# 30A.net
KiCad netlist of a schematic drawn in Altium Designer
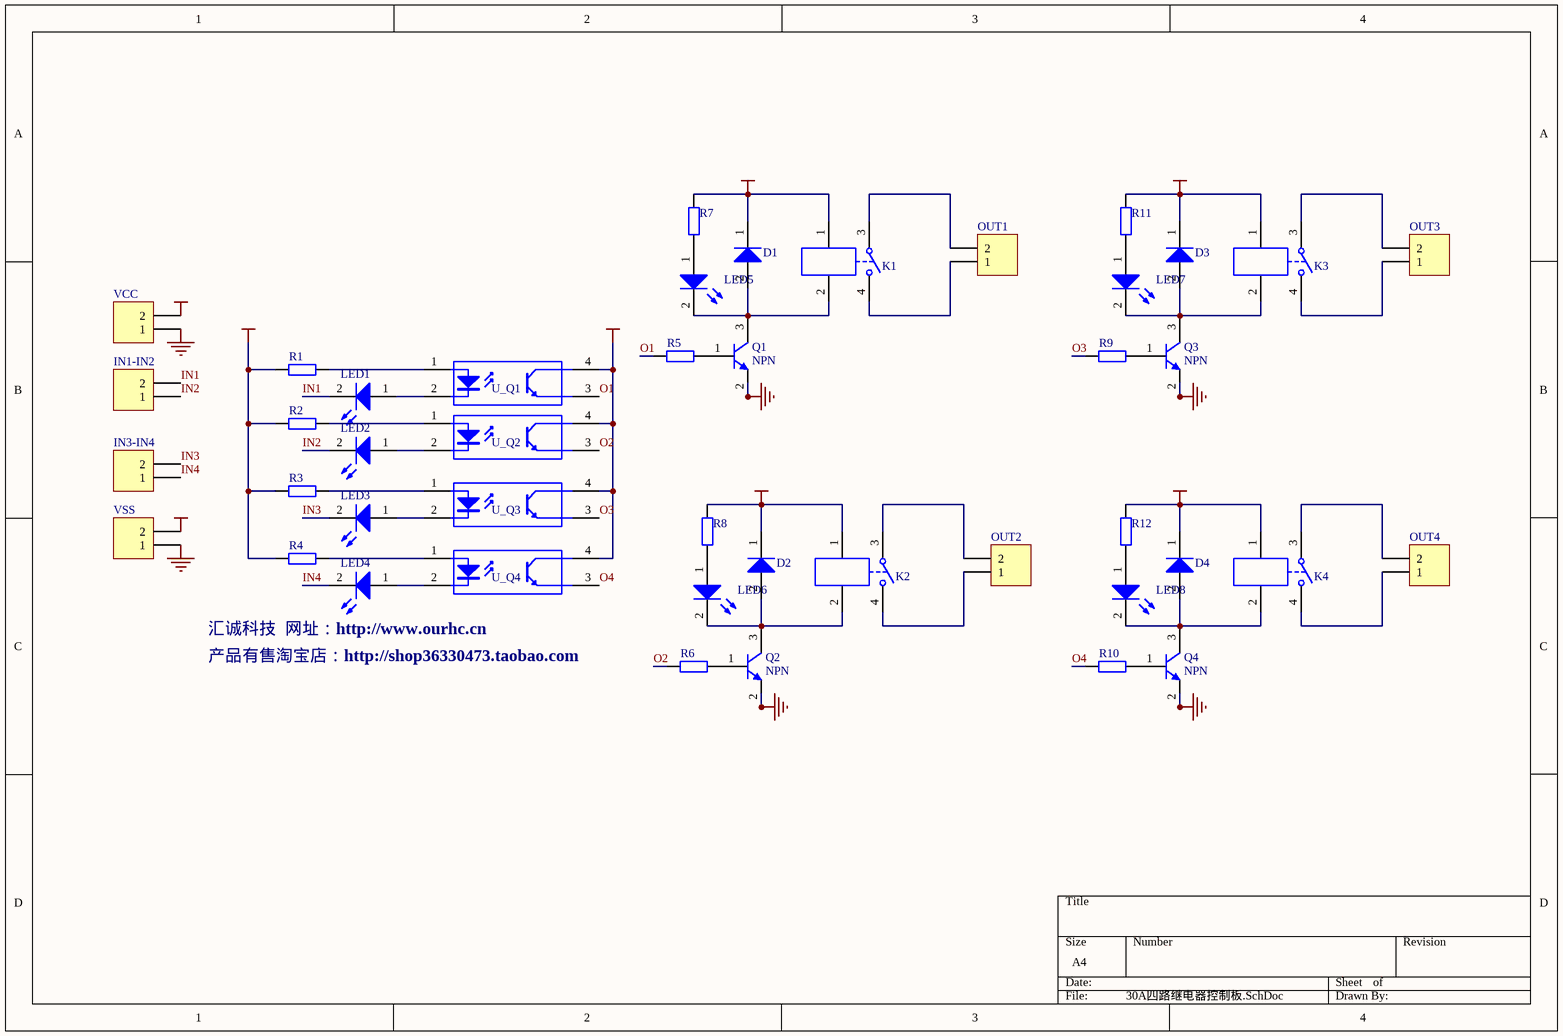
[diagram p0: 30A四路继电器控制板.SchDoc]

(export (version "E")
  (design (tool "Eeschema 10.0.6"))
  (components
    (comp (ref "D1")
      (value "ZL2JG")
      (footprint "7227")
      (description "整流二极管")
      (fields (field (name "PUBLISHER") "Altium Limited"))
      (libsource (lib "zxcourhc") (part "ZL2JG"))
    )
    (comp (ref "D2")
      (value "ZL2JG")
      (footprint "7227")
      (description "整流二极管")
      (fields (field (name "PUBLISHER") "Altium Limited"))
      (libsource (lib "zxcourhc") (part "ZL2JG"))
    )
    (comp (ref "D3")
      (value "ZL2JG")
      (footprint "7227")
      (description "整流二极管")
      (fields (field (name "PUBLISHER") "Altium Limited"))
      (libsource (lib "zxcourhc") (part "ZL2JG"))
    )
    (comp (ref "D4")
      (value "ZL2JG")
      (footprint "7227")
      (description "整流二极管")
      (fields (field (name "PUBLISHER") "Altium Limited"))
      (libsource (lib "zxcourhc") (part "ZL2JG"))
    )
    (comp (ref "IN1-IN2")
      (value "PZ_2")
      (footprint "KF8500-2")
      (description "排针——2")
      (fields (field (name "PUBLISHER") "Altium Limited"))
      (libsource (lib "zxcourhc") (part "PZ_2"))
    )
    (comp (ref "IN3-IN4")
      (value "PZ_2")
      (footprint "KF8500-2")
      (description "排针——2")
      (fields (field (name "PUBLISHER") "Altium Limited"))
      (libsource (lib "zxcourhc") (part "PZ_2"))
    )
    (comp (ref "K1")
      (value "JDQ1K")
      (footprint "SLA-12VDC-SL-A")
      (description "继电器一常开")
      (libsource (lib "zxcourhc") (part "JDQ1K"))
    )
    (comp (ref "K2")
      (value "JDQ1K")
      (footprint "SLA-12VDC-SL-A")
      (description "继电器一常开")
      (libsource (lib "zxcourhc") (part "JDQ1K"))
    )
    (comp (ref "K3")
      (value "JDQ1K")
      (footprint "SLA-12VDC-SL-A")
      (description "继电器一常开")
      (libsource (lib "zxcourhc") (part "JDQ1K"))
    )
    (comp (ref "K4")
      (value "JDQ1K")
      (footprint "SLA-12VDC-SL-A")
      (description "继电器一常开")
      (libsource (lib "zxcourhc") (part "JDQ1K"))
    )
    (comp (ref "LED1")
      (value "~")
      (footprint "LED_D")
      (description "发光二极管")
      (fields (field (name "PUBLISHER") "Altium Limited"))
      (libsource (lib "zxcourhc") (part "LED"))
    )
    (comp (ref "LED2")
      (value "~")
      (footprint "LED_D")
      (description "发光二极管")
      (fields (field (name "PUBLISHER") "Altium Limited"))
      (libsource (lib "zxcourhc") (part "LED"))
    )
    (comp (ref "LED3")
      (value "~")
      (footprint "LED_D")
      (description "发光二极管")
      (fields (field (name "PUBLISHER") "Altium Limited"))
      (libsource (lib "zxcourhc") (part "LED"))
    )
    (comp (ref "LED4")
      (value "~")
      (footprint "LED_D")
      (description "发光二极管")
      (fields (field (name "PUBLISHER") "Altium Limited"))
      (libsource (lib "zxcourhc") (part "LED"))
    )
    (comp (ref "LED5")
      (value "~")
      (footprint "LED_D")
      (description "发光二极管")
      (fields (field (name "PUBLISHER") "Altium Limited"))
      (libsource (lib "zxcourhc") (part "LED"))
    )
    (comp (ref "LED6")
      (value "~")
      (footprint "LED_D")
      (description "发光二极管")
      (fields (field (name "PUBLISHER") "Altium Limited"))
      (libsource (lib "zxcourhc") (part "LED"))
    )
    (comp (ref "LED7")
      (value "~")
      (footprint "LED_D")
      (description "发光二极管")
      (fields (field (name "PUBLISHER") "Altium Limited"))
      (libsource (lib "zxcourhc") (part "LED"))
    )
    (comp (ref "LED8")
      (value "~")
      (footprint "LED_D")
      (description "发光二极管")
      (fields (field (name "PUBLISHER") "Altium Limited"))
      (libsource (lib "zxcourhc") (part "LED"))
    )
    (comp (ref "OUT1")
      (value "PZ_2")
      (footprint "KF8500-2")
      (description "排针——2")
      (fields (field (name "PUBLISHER") "Altium Limited"))
      (libsource (lib "") (part "PZ_2_1"))
    )
    (comp (ref "OUT2")
      (value "PZ_2")
      (footprint "KF8500-2")
      (description "排针——2")
      (fields (field (name "PUBLISHER") "Altium Limited"))
      (libsource (lib "") (part "PZ_2_1"))
    )
    (comp (ref "OUT3")
      (value "PZ_2")
      (footprint "KF8500-2")
      (description "排针——2")
      (fields (field (name "PUBLISHER") "Altium Limited"))
      (libsource (lib "") (part "PZ_2_1"))
    )
    (comp (ref "OUT4")
      (value "PZ_2")
      (footprint "KF8500-2")
      (description "排针——2")
      (fields (field (name "PUBLISHER") "Altium Limited"))
      (libsource (lib "") (part "PZ_2_1"))
    )
    (comp (ref "Q1")
      (value "NPN")
      (footprint "SO-G3")
      (description "NPN Bipolar Transistor")
      (fields (field (name "PUBLISHER") "Altium Limited"))
      (libsource (lib "Miscellaneous Devices") (part "NPN"))
    )
    (comp (ref "Q2")
      (value "NPN")
      (footprint "SO-G3")
      (description "NPN Bipolar Transistor")
      (fields (field (name "PUBLISHER") "Altium Limited"))
      (libsource (lib "Miscellaneous Devices") (part "NPN"))
    )
    (comp (ref "Q3")
      (value "NPN")
      (footprint "SO-G3")
      (description "NPN Bipolar Transistor")
      (fields (field (name "PUBLISHER") "Altium Limited"))
      (libsource (lib "Miscellaneous Devices") (part "NPN"))
    )
    (comp (ref "Q4")
      (value "NPN")
      (footprint "SO-G3")
      (description "NPN Bipolar Transistor")
      (fields (field (name "PUBLISHER") "Altium Limited"))
      (libsource (lib "Miscellaneous Devices") (part "NPN"))
    )
    (comp (ref "R1")
      (value "Res")
      (footprint "TP-0805-R")
      (description "电阻")
      (fields (field (name "PUBLISHER") "Altium Limited"))
      (libsource (lib "zxcourhc") (part "Res"))
    )
    (comp (ref "R2")
      (value "Res")
      (footprint "TP-0805-R")
      (description "电阻")
      (fields (field (name "PUBLISHER") "Altium Limited"))
      (libsource (lib "zxcourhc") (part "Res"))
    )
    (comp (ref "R3")
      (value "Res")
      (footprint "TP-0805-R")
      (description "电阻")
      (fields (field (name "PUBLISHER") "Altium Limited"))
      (libsource (lib "zxcourhc") (part "Res"))
    )
    (comp (ref "R4")
      (value "Res")
      (footprint "TP-0805-R")
      (description "电阻")
      (fields (field (name "PUBLISHER") "Altium Limited"))
      (libsource (lib "zxcourhc") (part "Res"))
    )
    (comp (ref "R5")
      (value "Res")
      (footprint "TP-0805-R")
      (description "电阻")
      (fields (field (name "PUBLISHER") "Altium Limited"))
      (libsource (lib "zxcourhc") (part "Res"))
    )
    (comp (ref "R6")
      (value "Res")
      (footprint "TP-0805-R")
      (description "电阻")
      (fields (field (name "PUBLISHER") "Altium Limited"))
      (libsource (lib "zxcourhc") (part "Res"))
    )
    (comp (ref "R7")
      (value "Res")
      (footprint "TP-0805-R")
      (description "电阻")
      (fields (field (name "PUBLISHER") "Altium Limited"))
      (libsource (lib "") (part "Res_1"))
    )
    (comp (ref "R8")
      (value "Res")
      (footprint "TP-0805-R")
      (description "电阻")
      (fields (field (name "PUBLISHER") "Altium Limited"))
      (libsource (lib "") (part "Res_1"))
    )
    (comp (ref "R9")
      (value "Res")
      (footprint "TP-0805-R")
      (description "电阻")
      (fields (field (name "PUBLISHER") "Altium Limited"))
      (libsource (lib "zxcourhc") (part "Res"))
    )
    (comp (ref "R10")
      (value "Res")
      (footprint "TP-0805-R")
      (description "电阻")
      (fields (field (name "PUBLISHER") "Altium Limited"))
      (libsource (lib "zxcourhc") (part "Res"))
    )
    (comp (ref "R11")
      (value "Res")
      (footprint "TP-0805-R")
      (description "电阻")
      (fields (field (name "PUBLISHER") "Altium Limited"))
      (libsource (lib "") (part "Res_1"))
    )
    (comp (ref "R12")
      (value "Res")
      (footprint "TP-0805-R")
      (description "电阻")
      (fields (field (name "PUBLISHER") "Altium Limited"))
      (libsource (lib "") (part "Res_1"))
    )
    (comp (ref "U_Q1")
      (value "GO")
      (footprint "DIP-4")
      (description "光耦")
      (fields (field (name "PUBLISHER") "Altium Limited"))
      (libsource (lib "zxcourhc") (part "GO"))
    )
    (comp (ref "U_Q2")
      (value "GO")
      (footprint "DIP-4")
      (description "光耦")
      (fields (field (name "PUBLISHER") "Altium Limited"))
      (libsource (lib "zxcourhc") (part "GO"))
    )
    (comp (ref "U_Q3")
      (value "GO")
      (footprint "DIP-4")
      (description "光耦")
      (fields (field (name "PUBLISHER") "Altium Limited"))
      (libsource (lib "zxcourhc") (part "GO"))
    )
    (comp (ref "U_Q4")
      (value "GO")
      (footprint "DIP-4")
      (description "光耦")
      (fields (field (name "PUBLISHER") "Altium Limited"))
      (libsource (lib "zxcourhc") (part "GO"))
    )
    (comp (ref "VCC")
      (value "PZ_2")
      (footprint "KF8500-2")
      (description "排针——2")
      (fields (field (name "PUBLISHER") "Altium Limited"))
      (libsource (lib "zxcourhc") (part "PZ_2"))
    )
    (comp (ref "VSS")
      (value "PZ_2")
      (footprint "KF8500-2")
      (description "排针——2")
      (fields (field (name "PUBLISHER") "Altium Limited"))
      (libsource (lib "zxcourhc") (part "PZ_2"))
    )
  )
  (nets
    (net (code "1") (name "/IN1") (class "Default")
      (node (ref "IN1-IN2") (pin "2") (pinfunction "2_2") (pintype "passive"))
      (node (ref "LED1") (pin "2") (pinfunction "K_2") (pintype "passive"))
    )
    (net (code "2") (name "/IN2") (class "Default")
      (node (ref "IN1-IN2") (pin "1") (pinfunction "1_1") (pintype "passive"))
      (node (ref "LED2") (pin "2") (pinfunction "K_2") (pintype "passive"))
    )
    (net (code "3") (name "/IN3") (class "Default")
      (node (ref "IN3-IN4") (pin "2") (pinfunction "2_2") (pintype "passive"))
      (node (ref "LED3") (pin "2") (pinfunction "K_2") (pintype "passive"))
    )
    (net (code "4") (name "/IN4") (class "Default")
      (node (ref "IN3-IN4") (pin "1") (pinfunction "1_1") (pintype "passive"))
      (node (ref "LED4") (pin "2") (pinfunction "K_2") (pintype "passive"))
    )
    (net (code "5") (name "/O1") (class "Default")
      (node (ref "R5") (pin "2") (pinfunction "2_2") (pintype "passive"))
      (node (ref "U_Q1") (pin "3") (pinfunction "E_3") (pintype "passive"))
    )
    (net (code "6") (name "/O2") (class "Default")
      (node (ref "R6") (pin "2") (pinfunction "2_2") (pintype "passive"))
      (node (ref "U_Q2") (pin "3") (pinfunction "E_3") (pintype "passive"))
    )
    (net (code "7") (name "/O3") (class "Default")
      (node (ref "R9") (pin "2") (pinfunction "2_2") (pintype "passive"))
      (node (ref "U_Q3") (pin "3") (pinfunction "E_3") (pintype "passive"))
    )
    (net (code "8") (name "/O4") (class "Default")
      (node (ref "R10") (pin "2") (pinfunction "2_2") (pintype "passive"))
      (node (ref "U_Q4") (pin "3") (pinfunction "E_3") (pintype "passive"))
    )
    (net (code "9") (name "GND") (class "Default")
      (node (ref "Q1") (pin "2") (pinfunction "E_2") (pintype "passive"))
      (node (ref "Q2") (pin "2") (pinfunction "E_2") (pintype "passive"))
      (node (ref "Q3") (pin "2") (pinfunction "E_2") (pintype "passive"))
      (node (ref "Q4") (pin "2") (pinfunction "E_2") (pintype "passive"))
      (node (ref "VSS") (pin "1") (pinfunction "1_1") (pintype "passive"))
    )
    (net (code "10") (name "INGND") (class "Default")
      (node (ref "VCC") (pin "1") (pinfunction "1_1") (pintype "passive"))
    )
    (net (code "11") (name "Net-(D1-A)") (class "Default")
      (node (ref "D1") (pin "2") (pinfunction "A_2") (pintype "passive"))
      (node (ref "K1") (pin "2") (pinfunction "2_2") (pintype "passive"))
      (node (ref "LED5") (pin "2") (pinfunction "K_2") (pintype "passive"))
      (node (ref "Q1") (pin "3") (pinfunction "C_3") (pintype "passive"))
    )
    (net (code "12") (name "Net-(D2-A)") (class "Default")
      (node (ref "D2") (pin "2") (pinfunction "A_2") (pintype "passive"))
      (node (ref "K2") (pin "2") (pinfunction "2_2") (pintype "passive"))
      (node (ref "LED6") (pin "2") (pinfunction "K_2") (pintype "passive"))
      (node (ref "Q2") (pin "3") (pinfunction "C_3") (pintype "passive"))
    )
    (net (code "13") (name "Net-(D3-A)") (class "Default")
      (node (ref "D3") (pin "2") (pinfunction "A_2") (pintype "passive"))
      (node (ref "K3") (pin "2") (pinfunction "2_2") (pintype "passive"))
      (node (ref "LED7") (pin "2") (pinfunction "K_2") (pintype "passive"))
      (node (ref "Q3") (pin "3") (pinfunction "C_3") (pintype "passive"))
    )
    (net (code "14") (name "Net-(D4-A)") (class "Default")
      (node (ref "D4") (pin "2") (pinfunction "A_2") (pintype "passive"))
      (node (ref "K4") (pin "2") (pinfunction "2_2") (pintype "passive"))
      (node (ref "LED8") (pin "2") (pinfunction "K_2") (pintype "passive"))
      (node (ref "Q4") (pin "3") (pinfunction "C_3") (pintype "passive"))
    )
    (net (code "15") (name "Net-(K1-Pad3)") (class "Default")
      (node (ref "K1") (pin "3") (pinfunction "3_3") (pintype "passive"))
      (node (ref "OUT1") (pin "2") (pinfunction "2_2") (pintype "passive"))
    )
    (net (code "16") (name "Net-(K1-Pad4)") (class "Default")
      (node (ref "K1") (pin "4") (pinfunction "4_4") (pintype "passive"))
      (node (ref "OUT1") (pin "1") (pinfunction "1_1") (pintype "passive"))
    )
    (net (code "17") (name "Net-(K2-Pad3)") (class "Default")
      (node (ref "K2") (pin "3") (pinfunction "3_3") (pintype "passive"))
      (node (ref "OUT2") (pin "2") (pinfunction "2_2") (pintype "passive"))
    )
    (net (code "18") (name "Net-(K2-Pad4)") (class "Default")
      (node (ref "K2") (pin "4") (pinfunction "4_4") (pintype "passive"))
      (node (ref "OUT2") (pin "1") (pinfunction "1_1") (pintype "passive"))
    )
    (net (code "19") (name "Net-(K3-Pad3)") (class "Default")
      (node (ref "K3") (pin "3") (pinfunction "3_3") (pintype "passive"))
      (node (ref "OUT3") (pin "2") (pinfunction "2_2") (pintype "passive"))
    )
    (net (code "20") (name "Net-(K3-Pad4)") (class "Default")
      (node (ref "K3") (pin "4") (pinfunction "4_4") (pintype "passive"))
      (node (ref "OUT3") (pin "1") (pinfunction "1_1") (pintype "passive"))
    )
    (net (code "21") (name "Net-(K4-Pad3)") (class "Default")
      (node (ref "K4") (pin "3") (pinfunction "3_3") (pintype "passive"))
      (node (ref "OUT4") (pin "2") (pinfunction "2_2") (pintype "passive"))
    )
    (net (code "22") (name "Net-(K4-Pad4)") (class "Default")
      (node (ref "K4") (pin "4") (pinfunction "4_4") (pintype "passive"))
      (node (ref "OUT4") (pin "1") (pinfunction "1_1") (pintype "passive"))
    )
    (net (code "23") (name "Net-(LED1-A)") (class "Default")
      (node (ref "LED1") (pin "1") (pinfunction "A_1") (pintype "passive"))
      (node (ref "U_Q1") (pin "2") (pinfunction "K_2") (pintype "passive"))
    )
    (net (code "24") (name "Net-(LED2-A)") (class "Default")
      (node (ref "LED2") (pin "1") (pinfunction "A_1") (pintype "passive"))
      (node (ref "U_Q2") (pin "2") (pinfunction "K_2") (pintype "passive"))
    )
    (net (code "25") (name "Net-(LED3-A)") (class "Default")
      (node (ref "LED3") (pin "1") (pinfunction "A_1") (pintype "passive"))
      (node (ref "U_Q3") (pin "2") (pinfunction "K_2") (pintype "passive"))
    )
    (net (code "26") (name "Net-(LED4-A)") (class "Default")
      (node (ref "LED4") (pin "1") (pinfunction "A_1") (pintype "passive"))
      (node (ref "U_Q4") (pin "2") (pinfunction "K_2") (pintype "passive"))
    )
    (net (code "27") (name "Net-(LED5-A)") (class "Default")
      (node (ref "LED5") (pin "1") (pinfunction "A_1") (pintype "passive"))
      (node (ref "R7") (pin "1") (pinfunction "1_1") (pintype "passive"))
    )
    (net (code "28") (name "Net-(LED6-A)") (class "Default")
      (node (ref "LED6") (pin "1") (pinfunction "A_1") (pintype "passive"))
      (node (ref "R8") (pin "1") (pinfunction "1_1") (pintype "passive"))
    )
    (net (code "29") (name "Net-(LED7-A)") (class "Default")
      (node (ref "LED7") (pin "1") (pinfunction "A_1") (pintype "passive"))
      (node (ref "R11") (pin "1") (pinfunction "1_1") (pintype "passive"))
    )
    (net (code "30") (name "Net-(LED8-A)") (class "Default")
      (node (ref "LED8") (pin "1") (pinfunction "A_1") (pintype "passive"))
      (node (ref "R12") (pin "1") (pinfunction "1_1") (pintype "passive"))
    )
    (net (code "31") (name "Net-(Q1-B)") (class "Default")
      (node (ref "Q1") (pin "1") (pinfunction "B_1") (pintype "passive"))
      (node (ref "R5") (pin "1") (pinfunction "1_1") (pintype "passive"))
    )
    (net (code "32") (name "Net-(Q2-B)") (class "Default")
      (node (ref "Q2") (pin "1") (pinfunction "B_1") (pintype "passive"))
      (node (ref "R6") (pin "1") (pinfunction "1_1") (pintype "passive"))
    )
    (net (code "33") (name "Net-(Q3-B)") (class "Default")
      (node (ref "Q3") (pin "1") (pinfunction "B_1") (pintype "passive"))
      (node (ref "R9") (pin "1") (pinfunction "1_1") (pintype "passive"))
    )
    (net (code "34") (name "Net-(Q4-B)") (class "Default")
      (node (ref "Q4") (pin "1") (pinfunction "B_1") (pintype "passive"))
      (node (ref "R10") (pin "1") (pinfunction "1_1") (pintype "passive"))
    )
    (net (code "35") (name "Net-(U_Q1-A)") (class "Default")
      (node (ref "R1") (pin "1") (pinfunction "1_1") (pintype "passive"))
      (node (ref "U_Q1") (pin "1") (pinfunction "A_1") (pintype "passive"))
    )
    (net (code "36") (name "Net-(U_Q2-A)") (class "Default")
      (node (ref "R2") (pin "1") (pinfunction "1_1") (pintype "passive"))
      (node (ref "U_Q2") (pin "1") (pinfunction "A_1") (pintype "passive"))
    )
    (net (code "37") (name "Net-(U_Q3-A)") (class "Default")
      (node (ref "R3") (pin "1") (pinfunction "1_1") (pintype "passive"))
      (node (ref "U_Q3") (pin "1") (pinfunction "A_1") (pintype "passive"))
    )
    (net (code "38") (name "Net-(U_Q4-A)") (class "Default")
      (node (ref "R4") (pin "1") (pinfunction "1_1") (pintype "passive"))
      (node (ref "U_Q4") (pin "1") (pinfunction "A_1") (pintype "passive"))
    )
    (net (code "39") (name "VCC") (class "Default")
      (node (ref "R1") (pin "2") (pinfunction "2_2") (pintype "passive"))
      (node (ref "R2") (pin "2") (pinfunction "2_2") (pintype "passive"))
      (node (ref "R3") (pin "2") (pinfunction "2_2") (pintype "passive"))
      (node (ref "R4") (pin "2") (pinfunction "2_2") (pintype "passive"))
      (node (ref "VCC") (pin "2") (pinfunction "2_2") (pintype "passive"))
    )
    (net (code "40") (name "VSS") (class "Default")
      (node (ref "D1") (pin "1") (pinfunction "K_1") (pintype "passive"))
      (node (ref "D2") (pin "1") (pinfunction "K_1") (pintype "passive"))
      (node (ref "D3") (pin "1") (pinfunction "K_1") (pintype "passive"))
      (node (ref "D4") (pin "1") (pinfunction "K_1") (pintype "passive"))
      (node (ref "K1") (pin "1") (pinfunction "1_1") (pintype "passive"))
      (node (ref "K2") (pin "1") (pinfunction "1_1") (pintype "passive"))
      (node (ref "K3") (pin "1") (pinfunction "1_1") (pintype "passive"))
      (node (ref "K4") (pin "1") (pinfunction "1_1") (pintype "passive"))
      (node (ref "R11") (pin "2") (pinfunction "2_2") (pintype "passive"))
      (node (ref "R12") (pin "2") (pinfunction "2_2") (pintype "passive"))
      (node (ref "R7") (pin "2") (pinfunction "2_2") (pintype "passive"))
      (node (ref "R8") (pin "2") (pinfunction "2_2") (pintype "passive"))
      (node (ref "U_Q1") (pin "4") (pinfunction "C_4") (pintype "passive"))
      (node (ref "U_Q2") (pin "4") (pinfunction "C_4") (pintype "passive"))
      (node (ref "U_Q3") (pin "4") (pinfunction "C_4") (pintype "passive"))
      (node (ref "U_Q4") (pin "4") (pinfunction "C_4") (pintype "passive"))
      (node (ref "VSS") (pin "2") (pinfunction "2_2") (pintype "passive"))
    )
  )
)
